# Kello_Nixie.net
KiCad netlist of a schematic drawn in Altium Designer
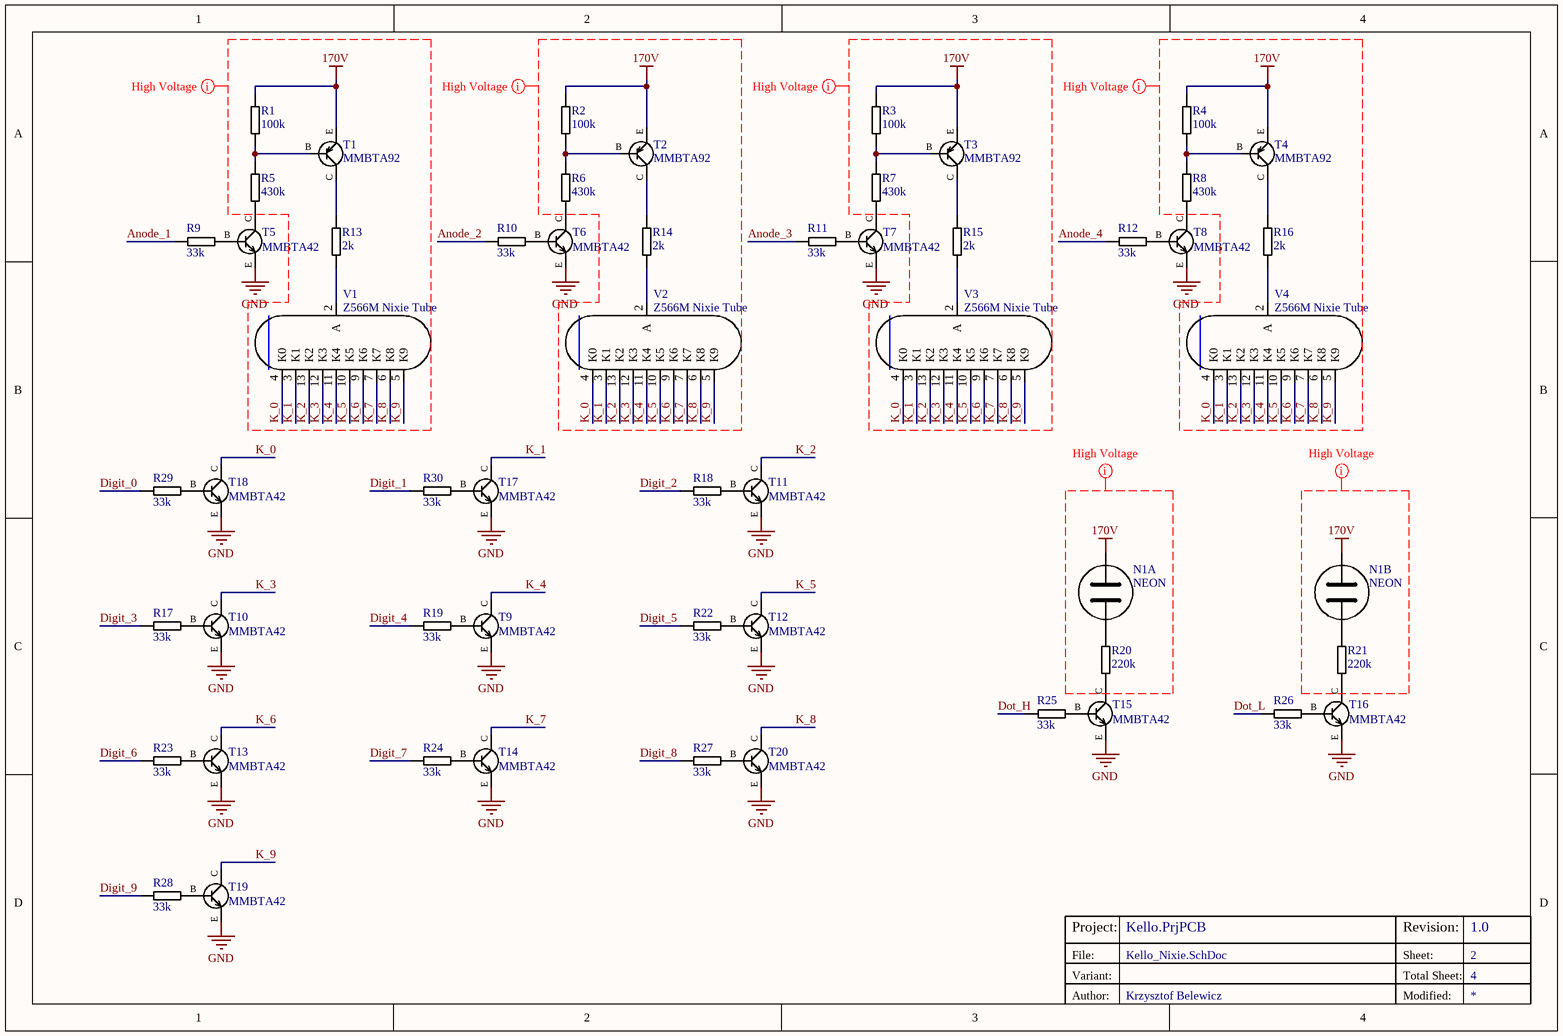
[diagram p0: Kello_Nixie.SchDoc]

(export (version "E")
  (design (tool "Eeschema 10.0.6"))
  (components
    (comp (ref "N1")
      (value "NEON")
      (footprint "NEON-9")
      (description "Neon Tube")
      (libsource (lib "") (part "NEON-9_1"))
    )
    (comp (ref "R1")
      (value "100k")
      (footprint "RESC1608N")
      (description "Resistor")
      (fields (field (name "TOLERANCE") "1%") (field (name "POWER") "0.1W"))
      (libsource (lib "RLC") (part "Resistor"))
    )
    (comp (ref "R2")
      (value "100k")
      (footprint "RESC1608N")
      (description "Resistor")
      (fields (field (name "TOLERANCE") "1%") (field (name "POWER") "0.1W"))
      (libsource (lib "RLC") (part "Resistor"))
    )
    (comp (ref "R3")
      (value "100k")
      (footprint "RESC1608N")
      (description "Resistor")
      (fields (field (name "TOLERANCE") "1%") (field (name "POWER") "0.1W"))
      (libsource (lib "RLC") (part "Resistor"))
    )
    (comp (ref "R4")
      (value "100k")
      (footprint "RESC1608N")
      (description "Resistor")
      (fields (field (name "TOLERANCE") "1%") (field (name "POWER") "0.1W"))
      (libsource (lib "RLC") (part "Resistor"))
    )
    (comp (ref "R5")
      (value "430k")
      (footprint "RESC1608N")
      (description "Resistor")
      (fields (field (name "TOLERANCE") "1%"))
      (libsource (lib "RLC") (part "Resistor"))
    )
    (comp (ref "R6")
      (value "430k")
      (footprint "RESC1608N")
      (description "Resistor")
      (fields (field (name "TOLERANCE") "1%"))
      (libsource (lib "RLC") (part "Resistor"))
    )
    (comp (ref "R7")
      (value "430k")
      (footprint "RESC1608N")
      (description "Resistor")
      (fields (field (name "TOLERANCE") "1%"))
      (libsource (lib "RLC") (part "Resistor"))
    )
    (comp (ref "R8")
      (value "430k")
      (footprint "RESC1608N")
      (description "Resistor")
      (fields (field (name "TOLERANCE") "1%"))
      (libsource (lib "RLC") (part "Resistor"))
    )
    (comp (ref "R9")
      (value "33k")
      (footprint "RESC1608N")
      (description "Resistor")
      (fields (field (name "TOLERANCE") "1%"))
      (libsource (lib "RLC") (part "Resistor"))
    )
    (comp (ref "R10")
      (value "33k")
      (footprint "RESC1608N")
      (description "Resistor")
      (fields (field (name "TOLERANCE") "1%"))
      (libsource (lib "RLC") (part "Resistor"))
    )
    (comp (ref "R11")
      (value "33k")
      (footprint "RESC1608N")
      (description "Resistor")
      (fields (field (name "TOLERANCE") "1%"))
      (libsource (lib "RLC") (part "Resistor"))
    )
    (comp (ref "R12")
      (value "33k")
      (footprint "RESC1608N")
      (description "Resistor")
      (fields (field (name "TOLERANCE") "1%"))
      (libsource (lib "RLC") (part "Resistor"))
    )
    (comp (ref "R13")
      (value "2k")
      (footprint "RESC1608N")
      (description "Resistor")
      (fields (field (name "TOLERANCE") "1%") (field (name "POWER") "0.1W"))
      (libsource (lib "RLC") (part "Resistor"))
    )
    (comp (ref "R14")
      (value "2k")
      (footprint "RESC1608N")
      (description "Resistor")
      (fields (field (name "TOLERANCE") "1%") (field (name "POWER") "0.1W"))
      (libsource (lib "RLC") (part "Resistor"))
    )
    (comp (ref "R15")
      (value "2k")
      (footprint "RESC1608N")
      (description "Resistor")
      (fields (field (name "TOLERANCE") "1%") (field (name "POWER") "0.1W"))
      (libsource (lib "RLC") (part "Resistor"))
    )
    (comp (ref "R16")
      (value "2k")
      (footprint "RESC1608N")
      (description "Resistor")
      (fields (field (name "TOLERANCE") "1%") (field (name "POWER") "0.1W"))
      (libsource (lib "RLC") (part "Resistor"))
    )
    (comp (ref "R17")
      (value "33k")
      (footprint "RESC1608N")
      (description "Resistor")
      (fields (field (name "TOLERANCE") "1%"))
      (libsource (lib "RLC") (part "Resistor"))
    )
    (comp (ref "R18")
      (value "33k")
      (footprint "RESC1608N")
      (description "Resistor")
      (fields (field (name "TOLERANCE") "1%"))
      (libsource (lib "RLC") (part "Resistor"))
    )
    (comp (ref "R19")
      (value "33k")
      (footprint "RESC1608N")
      (description "Resistor")
      (fields (field (name "TOLERANCE") "1%"))
      (libsource (lib "RLC") (part "Resistor"))
    )
    (comp (ref "R20")
      (value "220k")
      (footprint "RESC1608N")
      (description "Resistor")
      (fields (field (name "TOLERANCE") "1%"))
      (libsource (lib "RLC") (part "Resistor"))
    )
    (comp (ref "R21")
      (value "220k")
      (footprint "RESC1608N")
      (description "Resistor")
      (fields (field (name "TOLERANCE") "1%"))
      (libsource (lib "RLC") (part "Resistor"))
    )
    (comp (ref "R22")
      (value "33k")
      (footprint "RESC1608N")
      (description "Resistor")
      (fields (field (name "TOLERANCE") "1%"))
      (libsource (lib "RLC") (part "Resistor"))
    )
    (comp (ref "R23")
      (value "33k")
      (footprint "RESC1608N")
      (description "Resistor")
      (fields (field (name "TOLERANCE") "1%"))
      (libsource (lib "RLC") (part "Resistor"))
    )
    (comp (ref "R24")
      (value "33k")
      (footprint "RESC1608N")
      (description "Resistor")
      (fields (field (name "TOLERANCE") "1%"))
      (libsource (lib "RLC") (part "Resistor"))
    )
    (comp (ref "R25")
      (value "33k")
      (footprint "RESC1608N")
      (description "Resistor")
      (fields (field (name "TOLERANCE") "1%"))
      (libsource (lib "RLC") (part "Resistor"))
    )
    (comp (ref "R26")
      (value "33k")
      (footprint "RESC1608N")
      (description "Resistor")
      (fields (field (name "TOLERANCE") "1%"))
      (libsource (lib "RLC") (part "Resistor"))
    )
    (comp (ref "R27")
      (value "33k")
      (footprint "RESC1608N")
      (description "Resistor")
      (fields (field (name "TOLERANCE") "1%"))
      (libsource (lib "RLC") (part "Resistor"))
    )
    (comp (ref "R28")
      (value "33k")
      (footprint "RESC1608N")
      (description "Resistor")
      (fields (field (name "TOLERANCE") "1%"))
      (libsource (lib "RLC") (part "Resistor"))
    )
    (comp (ref "R29")
      (value "33k")
      (footprint "RESC1608N")
      (description "Resistor")
      (fields (field (name "TOLERANCE") "1%"))
      (libsource (lib "RLC") (part "Resistor"))
    )
    (comp (ref "R30")
      (value "33k")
      (footprint "RESC1608N")
      (description "Resistor")
      (fields (field (name "TOLERANCE") "1%"))
      (libsource (lib "RLC") (part "Resistor"))
    )
    (comp (ref "T1")
      (value "MMBTA92")
      (footprint "SOT23-3N")
      (description "PNP Transistor")
      (libsource (lib "Transistors") (part "2N5087"))
    )
    (comp (ref "T2")
      (value "MMBTA92")
      (footprint "SOT23-3N")
      (description "PNP Transistor")
      (libsource (lib "Transistors") (part "2N5087"))
    )
    (comp (ref "T3")
      (value "MMBTA92")
      (footprint "SOT23-3N")
      (description "PNP Transistor")
      (libsource (lib "Transistors") (part "2N5087"))
    )
    (comp (ref "T4")
      (value "MMBTA92")
      (footprint "SOT23-3N")
      (description "PNP Transistor")
      (libsource (lib "Transistors") (part "2N5087"))
    )
    (comp (ref "T5")
      (value "MMBTA42")
      (footprint "SOT23-3N")
      (description "NPN Transistor")
      (libsource (lib "Transistors") (part "2N3707"))
    )
    (comp (ref "T6")
      (value "MMBTA42")
      (footprint "SOT23-3N")
      (description "NPN Transistor")
      (libsource (lib "Transistors") (part "2N3707"))
    )
    (comp (ref "T7")
      (value "MMBTA42")
      (footprint "SOT23-3N")
      (description "NPN Transistor")
      (libsource (lib "Transistors") (part "2N3707"))
    )
    (comp (ref "T8")
      (value "MMBTA42")
      (footprint "SOT23-3N")
      (description "NPN Transistor")
      (libsource (lib "Transistors") (part "2N3707"))
    )
    (comp (ref "T9")
      (value "MMBTA42")
      (footprint "SOT23-3N")
      (description "NPN Transistor")
      (libsource (lib "Transistors") (part "2N3707"))
    )
    (comp (ref "T10")
      (value "MMBTA42")
      (footprint "SOT23-3N")
      (description "NPN Transistor")
      (libsource (lib "Transistors") (part "2N3707"))
    )
    (comp (ref "T11")
      (value "MMBTA42")
      (footprint "SOT23-3N")
      (description "NPN Transistor")
      (libsource (lib "Transistors") (part "2N3707"))
    )
    (comp (ref "T12")
      (value "MMBTA42")
      (footprint "SOT23-3N")
      (description "NPN Transistor")
      (libsource (lib "Transistors") (part "2N3707"))
    )
    (comp (ref "T13")
      (value "MMBTA42")
      (footprint "SOT23-3N")
      (description "NPN Transistor")
      (libsource (lib "Transistors") (part "2N3707"))
    )
    (comp (ref "T14")
      (value "MMBTA42")
      (footprint "SOT23-3N")
      (description "NPN Transistor")
      (libsource (lib "Transistors") (part "2N3707"))
    )
    (comp (ref "T15")
      (value "MMBTA42")
      (footprint "SOT23-3N")
      (description "NPN Transistor")
      (libsource (lib "Transistors") (part "2N3707"))
    )
    (comp (ref "T16")
      (value "MMBTA42")
      (footprint "SOT23-3N")
      (description "NPN Transistor")
      (libsource (lib "Transistors") (part "2N3707"))
    )
    (comp (ref "T17")
      (value "MMBTA42")
      (footprint "SOT23-3N")
      (description "NPN Transistor")
      (libsource (lib "Transistors") (part "2N3707"))
    )
    (comp (ref "T18")
      (value "MMBTA42")
      (footprint "SOT23-3N")
      (description "NPN Transistor")
      (libsource (lib "Transistors") (part "2N3707"))
    )
    (comp (ref "T19")
      (value "MMBTA42")
      (footprint "SOT23-3N")
      (description "NPN Transistor")
      (libsource (lib "Transistors") (part "2N3707"))
    )
    (comp (ref "T20")
      (value "MMBTA42")
      (footprint "SOT23-3N")
      (description "NPN Transistor")
      (libsource (lib "Transistors") (part "2N3707"))
    )
    (comp (ref "V1") (value "Z566M Nixie Tube") (footprint "Z566M") (libsource (lib "Z566M") (part "Z566M")))
    (comp (ref "V2") (value "Z566M Nixie Tube") (footprint "Z566M") (libsource (lib "Z566M") (part "Z566M")))
    (comp (ref "V3") (value "Z566M Nixie Tube") (footprint "Z566M") (libsource (lib "Z566M") (part "Z566M")))
    (comp (ref "V4") (value "Z566M Nixie Tube") (footprint "Z566M") (libsource (lib "Z566M") (part "Z566M")))
  )
  (nets
    (net (code "1") (name "/Anode_1") (class "Default")
      (node (ref "R9") (pin "1") (pinfunction "1_1") (pintype "passive"))
    )
    (net (code "2") (name "/Anode_2") (class "Default")
      (node (ref "R10") (pin "1") (pinfunction "1_1") (pintype "passive"))
    )
    (net (code "3") (name "/Anode_3") (class "Default")
      (node (ref "R11") (pin "1") (pinfunction "1_1") (pintype "passive"))
    )
    (net (code "4") (name "/Anode_4") (class "Default")
      (node (ref "R12") (pin "1") (pinfunction "1_1") (pintype "passive"))
    )
    (net (code "5") (name "/Digit_0") (class "Default")
      (node (ref "R29") (pin "1") (pinfunction "1_1") (pintype "passive"))
    )
    (net (code "6") (name "/Digit_1") (class "Default")
      (node (ref "R30") (pin "1") (pinfunction "1_1") (pintype "passive"))
    )
    (net (code "7") (name "/Digit_2") (class "Default")
      (node (ref "R18") (pin "1") (pinfunction "1_1") (pintype "passive"))
    )
    (net (code "8") (name "/Digit_3") (class "Default")
      (node (ref "R17") (pin "1") (pinfunction "1_1") (pintype "passive"))
    )
    (net (code "9") (name "/Digit_4") (class "Default")
      (node (ref "R19") (pin "1") (pinfunction "1_1") (pintype "passive"))
    )
    (net (code "10") (name "/Digit_5") (class "Default")
      (node (ref "R22") (pin "1") (pinfunction "1_1") (pintype "passive"))
    )
    (net (code "11") (name "/Digit_6") (class "Default")
      (node (ref "R23") (pin "1") (pinfunction "1_1") (pintype "passive"))
    )
    (net (code "12") (name "/Digit_7") (class "Default")
      (node (ref "R24") (pin "1") (pinfunction "1_1") (pintype "passive"))
    )
    (net (code "13") (name "/Digit_8") (class "Default")
      (node (ref "R27") (pin "1") (pinfunction "1_1") (pintype "passive"))
    )
    (net (code "14") (name "/Digit_9") (class "Default")
      (node (ref "R28") (pin "1") (pinfunction "1_1") (pintype "passive"))
    )
    (net (code "15") (name "/Dot_H") (class "Default")
      (node (ref "R25") (pin "1") (pinfunction "1_1") (pintype "passive"))
    )
    (net (code "16") (name "/Dot_L") (class "Default")
      (node (ref "R26") (pin "1") (pinfunction "1_1") (pintype "passive"))
    )
    (net (code "17") (name "/K_0") (class "Default")
      (node (ref "T18") (pin "C") (pinfunction "C_C") (pintype "passive"))
      (node (ref "V1") (pin "4") (pinfunction "K0_4") (pintype "passive"))
      (node (ref "V2") (pin "4") (pinfunction "K0_4") (pintype "passive"))
      (node (ref "V3") (pin "4") (pinfunction "K0_4") (pintype "passive"))
      (node (ref "V4") (pin "4") (pinfunction "K0_4") (pintype "passive"))
    )
    (net (code "18") (name "/K_1") (class "Default")
      (node (ref "T17") (pin "C") (pinfunction "C_C") (pintype "passive"))
      (node (ref "V1") (pin "3") (pinfunction "K1_3") (pintype "passive"))
      (node (ref "V2") (pin "3") (pinfunction "K1_3") (pintype "passive"))
      (node (ref "V3") (pin "3") (pinfunction "K1_3") (pintype "passive"))
      (node (ref "V4") (pin "3") (pinfunction "K1_3") (pintype "passive"))
    )
    (net (code "19") (name "/K_2") (class "Default")
      (node (ref "T11") (pin "C") (pinfunction "C_C") (pintype "passive"))
      (node (ref "V1") (pin "13") (pinfunction "K2_13") (pintype "passive"))
      (node (ref "V2") (pin "13") (pinfunction "K2_13") (pintype "passive"))
      (node (ref "V3") (pin "13") (pinfunction "K2_13") (pintype "passive"))
      (node (ref "V4") (pin "13") (pinfunction "K2_13") (pintype "passive"))
    )
    (net (code "20") (name "/K_3") (class "Default")
      (node (ref "T10") (pin "C") (pinfunction "C_C") (pintype "passive"))
      (node (ref "V1") (pin "12") (pinfunction "K3_12") (pintype "passive"))
      (node (ref "V2") (pin "12") (pinfunction "K3_12") (pintype "passive"))
      (node (ref "V3") (pin "12") (pinfunction "K3_12") (pintype "passive"))
      (node (ref "V4") (pin "12") (pinfunction "K3_12") (pintype "passive"))
    )
    (net (code "21") (name "/K_4") (class "Default")
      (node (ref "T9") (pin "C") (pinfunction "C_C") (pintype "passive"))
      (node (ref "V1") (pin "11") (pinfunction "K4_11") (pintype "passive"))
      (node (ref "V2") (pin "11") (pinfunction "K4_11") (pintype "passive"))
      (node (ref "V3") (pin "11") (pinfunction "K4_11") (pintype "passive"))
      (node (ref "V4") (pin "11") (pinfunction "K4_11") (pintype "passive"))
    )
    (net (code "22") (name "/K_5") (class "Default")
      (node (ref "T12") (pin "C") (pinfunction "C_C") (pintype "passive"))
      (node (ref "V1") (pin "10") (pinfunction "K5_10") (pintype "passive"))
      (node (ref "V2") (pin "10") (pinfunction "K5_10") (pintype "passive"))
      (node (ref "V3") (pin "10") (pinfunction "K5_10") (pintype "passive"))
      (node (ref "V4") (pin "10") (pinfunction "K5_10") (pintype "passive"))
    )
    (net (code "23") (name "/K_6") (class "Default")
      (node (ref "T13") (pin "C") (pinfunction "C_C") (pintype "passive"))
      (node (ref "V1") (pin "9") (pinfunction "K6_9") (pintype "passive"))
      (node (ref "V2") (pin "9") (pinfunction "K6_9") (pintype "passive"))
      (node (ref "V3") (pin "9") (pinfunction "K6_9") (pintype "passive"))
      (node (ref "V4") (pin "9") (pinfunction "K6_9") (pintype "passive"))
    )
    (net (code "24") (name "/K_7") (class "Default")
      (node (ref "T14") (pin "C") (pinfunction "C_C") (pintype "passive"))
      (node (ref "V1") (pin "7") (pinfunction "K7_7") (pintype "passive"))
      (node (ref "V2") (pin "7") (pinfunction "K7_7") (pintype "passive"))
      (node (ref "V3") (pin "7") (pinfunction "K7_7") (pintype "passive"))
      (node (ref "V4") (pin "7") (pinfunction "K7_7") (pintype "passive"))
    )
    (net (code "25") (name "/K_8") (class "Default")
      (node (ref "T20") (pin "C") (pinfunction "C_C") (pintype "passive"))
      (node (ref "V1") (pin "6") (pinfunction "K8_6") (pintype "passive"))
      (node (ref "V2") (pin "6") (pinfunction "K8_6") (pintype "passive"))
      (node (ref "V3") (pin "6") (pinfunction "K8_6") (pintype "passive"))
      (node (ref "V4") (pin "6") (pinfunction "K8_6") (pintype "passive"))
    )
    (net (code "26") (name "/K_9") (class "Default")
      (node (ref "T19") (pin "C") (pinfunction "C_C") (pintype "passive"))
      (node (ref "V1") (pin "5") (pinfunction "K9_5") (pintype "passive"))
      (node (ref "V2") (pin "5") (pinfunction "K9_5") (pintype "passive"))
      (node (ref "V3") (pin "5") (pinfunction "K9_5") (pintype "passive"))
      (node (ref "V4") (pin "5") (pinfunction "K9_5") (pintype "passive"))
    )
    (net (code "27") (name "170V") (class "Default")
      (node (ref "N1") (pin "2") (pinfunction "2_2") (pintype "passive"))
      (node (ref "R1") (pin "1") (pinfunction "1_1") (pintype "passive"))
      (node (ref "R2") (pin "1") (pinfunction "1_1") (pintype "passive"))
      (node (ref "R3") (pin "1") (pinfunction "1_1") (pintype "passive"))
      (node (ref "R4") (pin "1") (pinfunction "1_1") (pintype "passive"))
      (node (ref "T1") (pin "E") (pinfunction "E_E") (pintype "passive"))
      (node (ref "T2") (pin "E") (pinfunction "E_E") (pintype "passive"))
      (node (ref "T3") (pin "E") (pinfunction "E_E") (pintype "passive"))
      (node (ref "T4") (pin "E") (pinfunction "E_E") (pintype "passive"))
    )
    (net (code "28") (name "GND") (class "Default")
      (node (ref "T10") (pin "E") (pinfunction "E_E") (pintype "passive"))
      (node (ref "T11") (pin "E") (pinfunction "E_E") (pintype "passive"))
      (node (ref "T12") (pin "E") (pinfunction "E_E") (pintype "passive"))
      (node (ref "T13") (pin "E") (pinfunction "E_E") (pintype "passive"))
      (node (ref "T14") (pin "E") (pinfunction "E_E") (pintype "passive"))
      (node (ref "T15") (pin "E") (pinfunction "E_E") (pintype "passive"))
      (node (ref "T16") (pin "E") (pinfunction "E_E") (pintype "passive"))
      (node (ref "T17") (pin "E") (pinfunction "E_E") (pintype "passive"))
      (node (ref "T18") (pin "E") (pinfunction "E_E") (pintype "passive"))
      (node (ref "T19") (pin "E") (pinfunction "E_E") (pintype "passive"))
      (node (ref "T20") (pin "E") (pinfunction "E_E") (pintype "passive"))
      (node (ref "T5") (pin "E") (pinfunction "E_E") (pintype "passive"))
      (node (ref "T6") (pin "E") (pinfunction "E_E") (pintype "passive"))
      (node (ref "T7") (pin "E") (pinfunction "E_E") (pintype "passive"))
      (node (ref "T8") (pin "E") (pinfunction "E_E") (pintype "passive"))
      (node (ref "T9") (pin "E") (pinfunction "E_E") (pintype "passive"))
    )
    (net (code "29") (name "Net-(N1-Pad1)") (class "Default")
      (node (ref "N1") (pin "1") (pinfunction "1_1") (pintype "passive"))
      (node (ref "R20") (pin "1") (pinfunction "1_1") (pintype "passive"))
    )
    (net (code "30") (name "Net-(N1-Pad3)") (class "Default")
      (node (ref "N1") (pin "3") (pinfunction "3_3") (pintype "passive"))
      (node (ref "R21") (pin "1") (pinfunction "1_1") (pintype "passive"))
    )
    (net (code "31") (name "Net-(R1-Pad2)") (class "Default")
      (node (ref "R1") (pin "2") (pinfunction "2_2") (pintype "passive"))
      (node (ref "R5") (pin "1") (pinfunction "1_1") (pintype "passive"))
      (node (ref "T1") (pin "B") (pinfunction "B_B") (pintype "passive"))
    )
    (net (code "32") (name "Net-(R2-Pad2)") (class "Default")
      (node (ref "R2") (pin "2") (pinfunction "2_2") (pintype "passive"))
      (node (ref "R6") (pin "1") (pinfunction "1_1") (pintype "passive"))
      (node (ref "T2") (pin "B") (pinfunction "B_B") (pintype "passive"))
    )
    (net (code "33") (name "Net-(R3-Pad2)") (class "Default")
      (node (ref "R3") (pin "2") (pinfunction "2_2") (pintype "passive"))
      (node (ref "R7") (pin "1") (pinfunction "1_1") (pintype "passive"))
      (node (ref "T3") (pin "B") (pinfunction "B_B") (pintype "passive"))
    )
    (net (code "34") (name "Net-(R4-Pad2)") (class "Default")
      (node (ref "R4") (pin "2") (pinfunction "2_2") (pintype "passive"))
      (node (ref "R8") (pin "1") (pinfunction "1_1") (pintype "passive"))
      (node (ref "T4") (pin "B") (pinfunction "B_B") (pintype "passive"))
    )
    (net (code "35") (name "Net-(R5-Pad2)") (class "Default")
      (node (ref "R5") (pin "2") (pinfunction "2_2") (pintype "passive"))
      (node (ref "T5") (pin "C") (pinfunction "C_C") (pintype "passive"))
    )
    (net (code "36") (name "Net-(R6-Pad2)") (class "Default")
      (node (ref "R6") (pin "2") (pinfunction "2_2") (pintype "passive"))
      (node (ref "T6") (pin "C") (pinfunction "C_C") (pintype "passive"))
    )
    (net (code "37") (name "Net-(R7-Pad2)") (class "Default")
      (node (ref "R7") (pin "2") (pinfunction "2_2") (pintype "passive"))
      (node (ref "T7") (pin "C") (pinfunction "C_C") (pintype "passive"))
    )
    (net (code "38") (name "Net-(R8-Pad2)") (class "Default")
      (node (ref "R8") (pin "2") (pinfunction "2_2") (pintype "passive"))
      (node (ref "T8") (pin "C") (pinfunction "C_C") (pintype "passive"))
    )
    (net (code "39") (name "Net-(R9-Pad2)") (class "Default")
      (node (ref "R9") (pin "2") (pinfunction "2_2") (pintype "passive"))
      (node (ref "T5") (pin "B") (pinfunction "B_B") (pintype "passive"))
    )
    (net (code "40") (name "Net-(R10-Pad2)") (class "Default")
      (node (ref "R10") (pin "2") (pinfunction "2_2") (pintype "passive"))
      (node (ref "T6") (pin "B") (pinfunction "B_B") (pintype "passive"))
    )
    (net (code "41") (name "Net-(R11-Pad2)") (class "Default")
      (node (ref "R11") (pin "2") (pinfunction "2_2") (pintype "passive"))
      (node (ref "T7") (pin "B") (pinfunction "B_B") (pintype "passive"))
    )
    (net (code "42") (name "Net-(R12-Pad2)") (class "Default")
      (node (ref "R12") (pin "2") (pinfunction "2_2") (pintype "passive"))
      (node (ref "T8") (pin "B") (pinfunction "B_B") (pintype "passive"))
    )
    (net (code "43") (name "Net-(R13-Pad1)") (class "Default")
      (node (ref "R13") (pin "1") (pinfunction "1_1") (pintype "passive"))
      (node (ref "T1") (pin "C") (pinfunction "C_C") (pintype "passive"))
    )
    (net (code "44") (name "Net-(R14-Pad1)") (class "Default")
      (node (ref "R14") (pin "1") (pinfunction "1_1") (pintype "passive"))
      (node (ref "T2") (pin "C") (pinfunction "C_C") (pintype "passive"))
    )
    (net (code "45") (name "Net-(R15-Pad1)") (class "Default")
      (node (ref "R15") (pin "1") (pinfunction "1_1") (pintype "passive"))
      (node (ref "T3") (pin "C") (pinfunction "C_C") (pintype "passive"))
    )
    (net (code "46") (name "Net-(R16-Pad1)") (class "Default")
      (node (ref "R16") (pin "1") (pinfunction "1_1") (pintype "passive"))
      (node (ref "T4") (pin "C") (pinfunction "C_C") (pintype "passive"))
    )
    (net (code "47") (name "Net-(R17-Pad2)") (class "Default")
      (node (ref "R17") (pin "2") (pinfunction "2_2") (pintype "passive"))
      (node (ref "T10") (pin "B") (pinfunction "B_B") (pintype "passive"))
    )
    (net (code "48") (name "Net-(R18-Pad2)") (class "Default")
      (node (ref "R18") (pin "2") (pinfunction "2_2") (pintype "passive"))
      (node (ref "T11") (pin "B") (pinfunction "B_B") (pintype "passive"))
    )
    (net (code "49") (name "Net-(R19-Pad2)") (class "Default")
      (node (ref "R19") (pin "2") (pinfunction "2_2") (pintype "passive"))
      (node (ref "T9") (pin "B") (pinfunction "B_B") (pintype "passive"))
    )
    (net (code "50") (name "Net-(R20-Pad2)") (class "Default")
      (node (ref "R20") (pin "2") (pinfunction "2_2") (pintype "passive"))
      (node (ref "T15") (pin "C") (pinfunction "C_C") (pintype "passive"))
    )
    (net (code "51") (name "Net-(R21-Pad2)") (class "Default")
      (node (ref "R21") (pin "2") (pinfunction "2_2") (pintype "passive"))
      (node (ref "T16") (pin "C") (pinfunction "C_C") (pintype "passive"))
    )
    (net (code "52") (name "Net-(R22-Pad2)") (class "Default")
      (node (ref "R22") (pin "2") (pinfunction "2_2") (pintype "passive"))
      (node (ref "T12") (pin "B") (pinfunction "B_B") (pintype "passive"))
    )
    (net (code "53") (name "Net-(R23-Pad2)") (class "Default")
      (node (ref "R23") (pin "2") (pinfunction "2_2") (pintype "passive"))
      (node (ref "T13") (pin "B") (pinfunction "B_B") (pintype "passive"))
    )
    (net (code "54") (name "Net-(R24-Pad2)") (class "Default")
      (node (ref "R24") (pin "2") (pinfunction "2_2") (pintype "passive"))
      (node (ref "T14") (pin "B") (pinfunction "B_B") (pintype "passive"))
    )
    (net (code "55") (name "Net-(R25-Pad2)") (class "Default")
      (node (ref "R25") (pin "2") (pinfunction "2_2") (pintype "passive"))
      (node (ref "T15") (pin "B") (pinfunction "B_B") (pintype "passive"))
    )
    (net (code "56") (name "Net-(R26-Pad2)") (class "Default")
      (node (ref "R26") (pin "2") (pinfunction "2_2") (pintype "passive"))
      (node (ref "T16") (pin "B") (pinfunction "B_B") (pintype "passive"))
    )
    (net (code "57") (name "Net-(R27-Pad2)") (class "Default")
      (node (ref "R27") (pin "2") (pinfunction "2_2") (pintype "passive"))
      (node (ref "T20") (pin "B") (pinfunction "B_B") (pintype "passive"))
    )
    (net (code "58") (name "Net-(R28-Pad2)") (class "Default")
      (node (ref "R28") (pin "2") (pinfunction "2_2") (pintype "passive"))
      (node (ref "T19") (pin "B") (pinfunction "B_B") (pintype "passive"))
    )
    (net (code "59") (name "Net-(R29-Pad2)") (class "Default")
      (node (ref "R29") (pin "2") (pinfunction "2_2") (pintype "passive"))
      (node (ref "T18") (pin "B") (pinfunction "B_B") (pintype "passive"))
    )
    (net (code "60") (name "Net-(R30-Pad2)") (class "Default")
      (node (ref "R30") (pin "2") (pinfunction "2_2") (pintype "passive"))
      (node (ref "T17") (pin "B") (pinfunction "B_B") (pintype "passive"))
    )
    (net (code "61") (name "Net-(V1-A)") (class "Default")
      (node (ref "R13") (pin "2") (pinfunction "2_2") (pintype "passive"))
      (node (ref "V1") (pin "2") (pinfunction "A_2") (pintype "power_in"))
    )
    (net (code "62") (name "Net-(V2-A)") (class "Default")
      (node (ref "R14") (pin "2") (pinfunction "2_2") (pintype "passive"))
      (node (ref "V2") (pin "2") (pinfunction "A_2") (pintype "power_in"))
    )
    (net (code "63") (name "Net-(V3-A)") (class "Default")
      (node (ref "R15") (pin "2") (pinfunction "2_2") (pintype "passive"))
      (node (ref "V3") (pin "2") (pinfunction "A_2") (pintype "power_in"))
    )
    (net (code "64") (name "Net-(V4-A)") (class "Default")
      (node (ref "R16") (pin "2") (pinfunction "2_2") (pintype "passive"))
      (node (ref "V4") (pin "2") (pinfunction "A_2") (pintype "power_in"))
    )
  )
)
